# balancedphotodiode.net
KiCad netlist of a schematic drawn in EAGLE
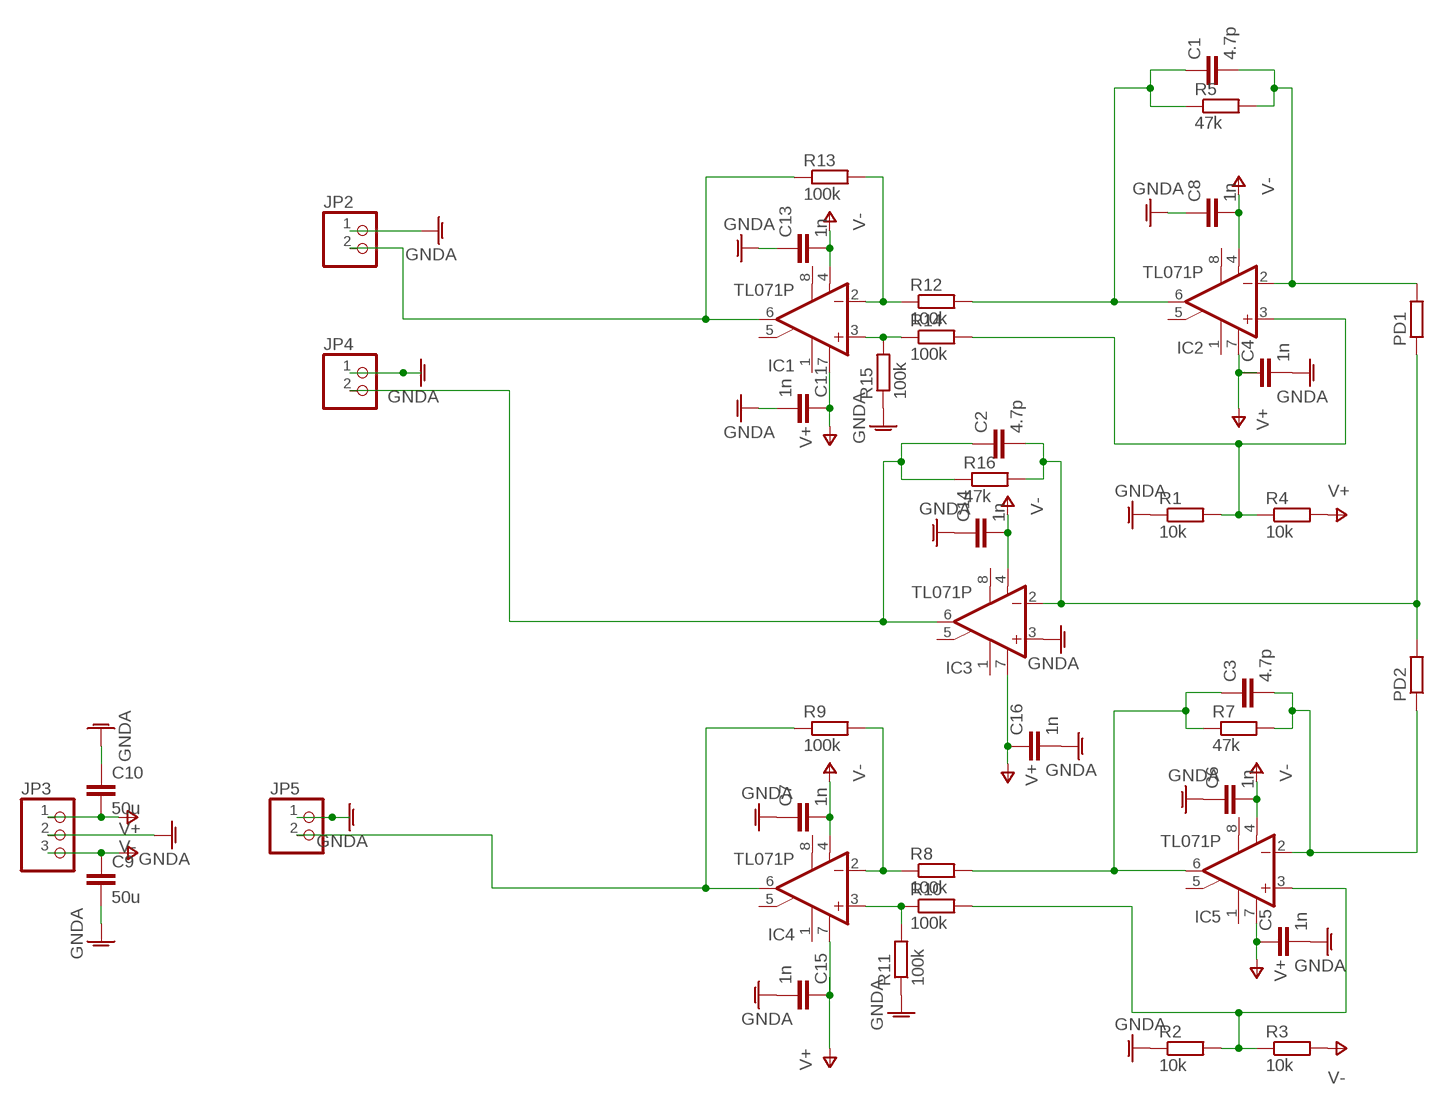
[diagram p0: schematic, sheet 1]

(export (version "E")
  (design (tool "Eeschema 10.0.6"))
  (components
    (comp (ref "C1")
      (value "4.7p")
      (footprint "eagle-import:C025-024X044")
      (libsource (lib "eagle-import") (part "C-EU025-024X044"))
    )
    (comp (ref "C2")
      (value "4.7p")
      (footprint "eagle-import:C025-024X044")
      (libsource (lib "eagle-import") (part "C-EU025-024X044"))
    )
    (comp (ref "C3")
      (value "4.7p")
      (footprint "eagle-import:C025-024X044")
      (libsource (lib "eagle-import") (part "C-EU025-024X044"))
    )
    (comp (ref "C4")
      (value "1n")
      (footprint "eagle-import:C1206")
      (libsource (lib "eagle-import") (part "C-EUC1206"))
    )
    (comp (ref "C5")
      (value "1n")
      (footprint "eagle-import:C1206")
      (libsource (lib "eagle-import") (part "C-EUC1206"))
    )
    (comp (ref "C6")
      (value "1n")
      (footprint "eagle-import:C1206")
      (libsource (lib "eagle-import") (part "C-EUC1206"))
    )
    (comp (ref "C7")
      (value "1n")
      (footprint "eagle-import:C1206")
      (libsource (lib "eagle-import") (part "C-EUC1206"))
    )
    (comp (ref "C8")
      (value "1n")
      (footprint "eagle-import:C1206")
      (libsource (lib "eagle-import") (part "C-EUC1206"))
    )
    (comp (ref "C9")
      (value "50u")
      (footprint "eagle-import:C025-050X050")
      (libsource (lib "eagle-import") (part "C-EU025-050X050"))
    )
    (comp (ref "C10")
      (value "50u")
      (footprint "eagle-import:C025-050X050")
      (libsource (lib "eagle-import") (part "C-EU025-050X050"))
    )
    (comp (ref "C11")
      (value "1n")
      (footprint "eagle-import:C1206")
      (libsource (lib "eagle-import") (part "C-EUC1206"))
    )
    (comp (ref "C13")
      (value "1n")
      (footprint "eagle-import:C1206")
      (libsource (lib "eagle-import") (part "C-EUC1206"))
    )
    (comp (ref "C14")
      (value "1n")
      (footprint "eagle-import:C1206")
      (libsource (lib "eagle-import") (part "C-EUC1206"))
    )
    (comp (ref "C15")
      (value "1n")
      (footprint "eagle-import:C1206")
      (libsource (lib "eagle-import") (part "C-EUC1206"))
    )
    (comp (ref "C16")
      (value "1n")
      (footprint "eagle-import:C1206")
      (libsource (lib "eagle-import") (part "C-EUC1206"))
    )
    (comp (ref "IC1")
      (value "TL071P")
      (footprint "eagle-import:DIL08")
      (libsource (lib "eagle-import") (part "TL071P"))
    )
    (comp (ref "IC2")
      (value "TL071P")
      (footprint "eagle-import:DIL08")
      (libsource (lib "eagle-import") (part "TL071P"))
    )
    (comp (ref "IC3")
      (value "TL071P")
      (footprint "eagle-import:DIL08")
      (libsource (lib "eagle-import") (part "TL071P"))
    )
    (comp (ref "IC4")
      (value "TL071P")
      (footprint "eagle-import:DIL08")
      (libsource (lib "eagle-import") (part "TL071P"))
    )
    (comp (ref "IC5")
      (value "TL071P")
      (footprint "eagle-import:DIL08")
      (libsource (lib "eagle-import") (part "TL071P"))
    )
    (comp (ref "JP2")
      (value "PINHD-1X2/90")
      (footprint "eagle-import:1X02_90")
      (libsource (lib "eagle-import") (part "PINHD-1X2/90"))
    )
    (comp (ref "JP3")
      (value "PINHD-1X3/90")
      (footprint "eagle-import:1X03_90")
      (libsource (lib "eagle-import") (part "PINHD-1X3/90"))
    )
    (comp (ref "JP4")
      (value "PINHD-1X2/90")
      (footprint "eagle-import:1X02_90")
      (libsource (lib "eagle-import") (part "PINHD-1X2/90"))
    )
    (comp (ref "JP5")
      (value "PINHD-1X2/90")
      (footprint "eagle-import:1X02_90")
      (libsource (lib "eagle-import") (part "PINHD-1X2/90"))
    )
    (comp (ref "PD1")
      (value "R-EU_0204/2V")
      (footprint "eagle-import:0204V")
      (libsource (lib "eagle-import") (part "R-EU_0204/2V"))
    )
    (comp (ref "PD2")
      (value "R-EU_0204/2V")
      (footprint "eagle-import:0204V")
      (libsource (lib "eagle-import") (part "R-EU_0204/2V"))
    )
    (comp (ref "R1")
      (value "10k")
      (footprint "eagle-import:0207_7")
      (libsource (lib "eagle-import") (part "R-EU_0207/7"))
    )
    (comp (ref "R2")
      (value "10k")
      (footprint "eagle-import:0207_7")
      (libsource (lib "eagle-import") (part "R-EU_0207/7"))
    )
    (comp (ref "R3")
      (value "10k")
      (footprint "eagle-import:0207_7")
      (libsource (lib "eagle-import") (part "R-EU_0207/7"))
    )
    (comp (ref "R4")
      (value "10k")
      (footprint "eagle-import:0207_7")
      (libsource (lib "eagle-import") (part "R-EU_0207/7"))
    )
    (comp (ref "R5")
      (value "47k")
      (footprint "eagle-import:0207_7")
      (libsource (lib "eagle-import") (part "R-EU_0207/7"))
    )
    (comp (ref "R7")
      (value "47k")
      (footprint "eagle-import:0207_7")
      (libsource (lib "eagle-import") (part "R-EU_0207/7"))
    )
    (comp (ref "R8")
      (value "100k")
      (footprint "eagle-import:0207_7")
      (libsource (lib "eagle-import") (part "R-EU_0207/7"))
    )
    (comp (ref "R9")
      (value "100k")
      (footprint "eagle-import:0207_7")
      (libsource (lib "eagle-import") (part "R-EU_0207/7"))
    )
    (comp (ref "R10")
      (value "100k")
      (footprint "eagle-import:0207_7")
      (libsource (lib "eagle-import") (part "R-EU_0207/7"))
    )
    (comp (ref "R11")
      (value "100k")
      (footprint "eagle-import:0207_7")
      (libsource (lib "eagle-import") (part "R-EU_0207/7"))
    )
    (comp (ref "R12")
      (value "100k")
      (footprint "eagle-import:0207_7")
      (libsource (lib "eagle-import") (part "R-EU_0207/7"))
    )
    (comp (ref "R13")
      (value "100k")
      (footprint "eagle-import:0207_7")
      (libsource (lib "eagle-import") (part "R-EU_0207/7"))
    )
    (comp (ref "R14")
      (value "100k")
      (footprint "eagle-import:0207_7")
      (libsource (lib "eagle-import") (part "R-EU_0207/7"))
    )
    (comp (ref "R15")
      (value "100k")
      (footprint "eagle-import:0207_7")
      (libsource (lib "eagle-import") (part "R-EU_0207/7"))
    )
    (comp (ref "R16")
      (value "47k")
      (footprint "eagle-import:0207_7")
      (libsource (lib "eagle-import") (part "R-EU_0207/7"))
    )
  )
  (nets
    (net (code "1") (name "GNDA") (class "Default")
      (node (ref "C10") (pin "1") (pinfunction "1_1") (pintype "passive"))
      (node (ref "C11") (pin "2") (pinfunction "2_2") (pintype "passive"))
      (node (ref "C13") (pin "1") (pinfunction "1_1") (pintype "passive"))
      (node (ref "C14") (pin "1") (pinfunction "1_1") (pintype "passive"))
      (node (ref "C15") (pin "2") (pinfunction "2_2") (pintype "passive"))
      (node (ref "C16") (pin "2") (pinfunction "2_2") (pintype "passive"))
      (node (ref "C4") (pin "2") (pinfunction "2_2") (pintype "passive"))
      (node (ref "C5") (pin "2") (pinfunction "2_2") (pintype "passive"))
      (node (ref "C6") (pin "1") (pinfunction "1_1") (pintype "passive"))
      (node (ref "C7") (pin "1") (pinfunction "1_1") (pintype "passive"))
      (node (ref "C8") (pin "1") (pinfunction "1_1") (pintype "passive"))
      (node (ref "C9") (pin "2") (pinfunction "2_2") (pintype "passive"))
      (node (ref "IC3") (pin "3") (pinfunction "+IN_3") (pintype "input"))
      (node (ref "JP2") (pin "1") (pinfunction "1_1") (pintype "passive"))
      (node (ref "JP3") (pin "2") (pinfunction "2_2") (pintype "passive"))
      (node (ref "JP4") (pin "1") (pinfunction "1_1") (pintype "passive"))
      (node (ref "JP5") (pin "1") (pinfunction "1_1") (pintype "passive"))
      (node (ref "R1") (pin "1") (pinfunction "1_1") (pintype "passive"))
      (node (ref "R11") (pin "1") (pinfunction "1_1") (pintype "passive"))
      (node (ref "R15") (pin "1") (pinfunction "1_1") (pintype "passive"))
      (node (ref "R2") (pin "1") (pinfunction "1_1") (pintype "passive"))
    )
    (net (code "2") (name "Net-(IC1-+IN)") (class "Default")
      (node (ref "IC1") (pin "3") (pinfunction "+IN_3") (pintype "input"))
      (node (ref "R14") (pin "1") (pinfunction "1_1") (pintype "passive"))
      (node (ref "R15") (pin "2") (pinfunction "2_2") (pintype "passive"))
    )
    (net (code "3") (name "Net-(IC1--IN)") (class "Default")
      (node (ref "IC1") (pin "2") (pinfunction "-IN_2") (pintype "input"))
      (node (ref "R12") (pin "1") (pinfunction "1_1") (pintype "passive"))
      (node (ref "R13") (pin "2") (pinfunction "2_2") (pintype "passive"))
    )
    (net (code "4") (name "Net-(IC1-OUT)") (class "Default")
      (node (ref "IC1") (pin "6") (pinfunction "OUT_6") (pintype "output"))
      (node (ref "JP2") (pin "2") (pinfunction "2_2") (pintype "passive"))
      (node (ref "R13") (pin "1") (pinfunction "1_1") (pintype "passive"))
    )
    (net (code "5") (name "Net-(IC2-+IN)") (class "Default")
      (node (ref "IC2") (pin "3") (pinfunction "+IN_3") (pintype "input"))
      (node (ref "R1") (pin "2") (pinfunction "2_2") (pintype "passive"))
      (node (ref "R14") (pin "2") (pinfunction "2_2") (pintype "passive"))
      (node (ref "R4") (pin "1") (pinfunction "1_1") (pintype "passive"))
    )
    (net (code "6") (name "Net-(IC2--IN)") (class "Default")
      (node (ref "C1") (pin "2") (pinfunction "2_2") (pintype "passive"))
      (node (ref "IC2") (pin "2") (pinfunction "-IN_2") (pintype "input"))
      (node (ref "PD1") (pin "2") (pinfunction "2_2") (pintype "passive"))
      (node (ref "R5") (pin "2") (pinfunction "2_2") (pintype "passive"))
    )
    (net (code "7") (name "Net-(IC2-OUT)") (class "Default")
      (node (ref "C1") (pin "1") (pinfunction "1_1") (pintype "passive"))
      (node (ref "IC2") (pin "6") (pinfunction "OUT_6") (pintype "output"))
      (node (ref "R12") (pin "2") (pinfunction "2_2") (pintype "passive"))
      (node (ref "R5") (pin "1") (pinfunction "1_1") (pintype "passive"))
    )
    (net (code "8") (name "Net-(IC3--IN)") (class "Default")
      (node (ref "C2") (pin "2") (pinfunction "2_2") (pintype "passive"))
      (node (ref "IC3") (pin "2") (pinfunction "-IN_2") (pintype "input"))
      (node (ref "PD1") (pin "1") (pinfunction "1_1") (pintype "passive"))
      (node (ref "PD2") (pin "2") (pinfunction "2_2") (pintype "passive"))
      (node (ref "R16") (pin "2") (pinfunction "2_2") (pintype "passive"))
    )
    (net (code "9") (name "Net-(IC3-OUT)") (class "Default")
      (node (ref "C2") (pin "1") (pinfunction "1_1") (pintype "passive"))
      (node (ref "IC3") (pin "6") (pinfunction "OUT_6") (pintype "output"))
      (node (ref "JP4") (pin "2") (pinfunction "2_2") (pintype "passive"))
      (node (ref "R16") (pin "1") (pinfunction "1_1") (pintype "passive"))
    )
    (net (code "10") (name "Net-(IC4-+IN)") (class "Default")
      (node (ref "IC4") (pin "3") (pinfunction "+IN_3") (pintype "input"))
      (node (ref "R10") (pin "1") (pinfunction "1_1") (pintype "passive"))
      (node (ref "R11") (pin "2") (pinfunction "2_2") (pintype "passive"))
    )
    (net (code "11") (name "Net-(IC4--IN)") (class "Default")
      (node (ref "IC4") (pin "2") (pinfunction "-IN_2") (pintype "input"))
      (node (ref "R8") (pin "1") (pinfunction "1_1") (pintype "passive"))
      (node (ref "R9") (pin "2") (pinfunction "2_2") (pintype "passive"))
    )
    (net (code "12") (name "Net-(IC4-OUT)") (class "Default")
      (node (ref "IC4") (pin "6") (pinfunction "OUT_6") (pintype "output"))
      (node (ref "JP5") (pin "2") (pinfunction "2_2") (pintype "passive"))
      (node (ref "R9") (pin "1") (pinfunction "1_1") (pintype "passive"))
    )
    (net (code "13") (name "Net-(IC5-+IN)") (class "Default")
      (node (ref "IC5") (pin "3") (pinfunction "+IN_3") (pintype "input"))
      (node (ref "R10") (pin "2") (pinfunction "2_2") (pintype "passive"))
      (node (ref "R2") (pin "2") (pinfunction "2_2") (pintype "passive"))
      (node (ref "R3") (pin "1") (pinfunction "1_1") (pintype "passive"))
    )
    (net (code "14") (name "Net-(IC5--IN)") (class "Default")
      (node (ref "C3") (pin "2") (pinfunction "2_2") (pintype "passive"))
      (node (ref "IC5") (pin "2") (pinfunction "-IN_2") (pintype "input"))
      (node (ref "PD2") (pin "1") (pinfunction "1_1") (pintype "passive"))
      (node (ref "R7") (pin "2") (pinfunction "2_2") (pintype "passive"))
    )
    (net (code "15") (name "Net-(IC5-OUT)") (class "Default")
      (node (ref "C3") (pin "1") (pinfunction "1_1") (pintype "passive"))
      (node (ref "IC5") (pin "6") (pinfunction "OUT_6") (pintype "output"))
      (node (ref "R7") (pin "1") (pinfunction "1_1") (pintype "passive"))
      (node (ref "R8") (pin "2") (pinfunction "2_2") (pintype "passive"))
    )
    (net (code "16") (name "V+") (class "Default")
      (node (ref "C11") (pin "1") (pinfunction "1_1") (pintype "passive"))
      (node (ref "C15") (pin "1") (pinfunction "1_1") (pintype "passive"))
      (node (ref "C16") (pin "1") (pinfunction "1_1") (pintype "passive"))
      (node (ref "C4") (pin "1") (pinfunction "1_1") (pintype "passive"))
      (node (ref "C5") (pin "1") (pinfunction "1_1") (pintype "passive"))
      (node (ref "C9") (pin "1") (pinfunction "1_1") (pintype "passive"))
      (node (ref "IC1") (pin "7") (pinfunction "V+_7") (pintype "power_in"))
      (node (ref "IC2") (pin "7") (pinfunction "V+_7") (pintype "power_in"))
      (node (ref "IC3") (pin "7") (pinfunction "V+_7") (pintype "power_in"))
      (node (ref "IC4") (pin "7") (pinfunction "V+_7") (pintype "power_in"))
      (node (ref "IC5") (pin "7") (pinfunction "V+_7") (pintype "power_in"))
      (node (ref "JP3") (pin "3") (pinfunction "3_3") (pintype "passive"))
      (node (ref "R4") (pin "2") (pinfunction "2_2") (pintype "passive"))
    )
    (net (code "17") (name "V-") (class "Default")
      (node (ref "C10") (pin "2") (pinfunction "2_2") (pintype "passive"))
      (node (ref "C13") (pin "2") (pinfunction "2_2") (pintype "passive"))
      (node (ref "C14") (pin "2") (pinfunction "2_2") (pintype "passive"))
      (node (ref "C6") (pin "2") (pinfunction "2_2") (pintype "passive"))
      (node (ref "C7") (pin "2") (pinfunction "2_2") (pintype "passive"))
      (node (ref "C8") (pin "2") (pinfunction "2_2") (pintype "passive"))
      (node (ref "IC1") (pin "4") (pinfunction "V-_4") (pintype "power_in"))
      (node (ref "IC2") (pin "4") (pinfunction "V-_4") (pintype "power_in"))
      (node (ref "IC3") (pin "4") (pinfunction "V-_4") (pintype "power_in"))
      (node (ref "IC4") (pin "4") (pinfunction "V-_4") (pintype "power_in"))
      (node (ref "IC5") (pin "4") (pinfunction "V-_4") (pintype "power_in"))
      (node (ref "JP3") (pin "1") (pinfunction "1_1") (pintype "passive"))
      (node (ref "R3") (pin "2") (pinfunction "2_2") (pintype "passive"))
    )
    (net (code "18") (name "unconnected-(IC1-ON1-Pad1)") (class "Default")
      (node (ref "IC1") (pin "1") (pinfunction "ON1_1") (pintype "passive"))
    )
    (net (code "19") (name "unconnected-(IC1-ON2-Pad5)") (class "Default")
      (node (ref "IC1") (pin "5") (pinfunction "ON2_5") (pintype "passive"))
    )
    (net (code "20") (name "unconnected-(IC1-OPT-Pad8)") (class "Default")
      (node (ref "IC1") (pin "8") (pinfunction "OPT_8") (pintype "passive"))
    )
    (net (code "21") (name "unconnected-(IC2-ON1-Pad1)") (class "Default")
      (node (ref "IC2") (pin "1") (pinfunction "ON1_1") (pintype "passive"))
    )
    (net (code "22") (name "unconnected-(IC2-ON2-Pad5)") (class "Default")
      (node (ref "IC2") (pin "5") (pinfunction "ON2_5") (pintype "passive"))
    )
    (net (code "23") (name "unconnected-(IC2-OPT-Pad8)") (class "Default")
      (node (ref "IC2") (pin "8") (pinfunction "OPT_8") (pintype "passive"))
    )
    (net (code "24") (name "unconnected-(IC3-ON1-Pad1)") (class "Default")
      (node (ref "IC3") (pin "1") (pinfunction "ON1_1") (pintype "passive"))
    )
    (net (code "25") (name "unconnected-(IC3-ON2-Pad5)") (class "Default")
      (node (ref "IC3") (pin "5") (pinfunction "ON2_5") (pintype "passive"))
    )
    (net (code "26") (name "unconnected-(IC3-OPT-Pad8)") (class "Default")
      (node (ref "IC3") (pin "8") (pinfunction "OPT_8") (pintype "passive"))
    )
    (net (code "27") (name "unconnected-(IC4-ON1-Pad1)") (class "Default")
      (node (ref "IC4") (pin "1") (pinfunction "ON1_1") (pintype "passive"))
    )
    (net (code "28") (name "unconnected-(IC4-ON2-Pad5)") (class "Default")
      (node (ref "IC4") (pin "5") (pinfunction "ON2_5") (pintype "passive"))
    )
    (net (code "29") (name "unconnected-(IC4-OPT-Pad8)") (class "Default")
      (node (ref "IC4") (pin "8") (pinfunction "OPT_8") (pintype "passive"))
    )
    (net (code "30") (name "unconnected-(IC5-ON1-Pad1)") (class "Default")
      (node (ref "IC5") (pin "1") (pinfunction "ON1_1") (pintype "passive"))
    )
    (net (code "31") (name "unconnected-(IC5-ON2-Pad5)") (class "Default")
      (node (ref "IC5") (pin "5") (pinfunction "ON2_5") (pintype "passive"))
    )
    (net (code "32") (name "unconnected-(IC5-OPT-Pad8)") (class "Default")
      (node (ref "IC5") (pin "8") (pinfunction "OPT_8") (pintype "passive"))
    )
  )
)
